# 1_power.net
KiCad netlist of a schematic drawn in Altium Designer
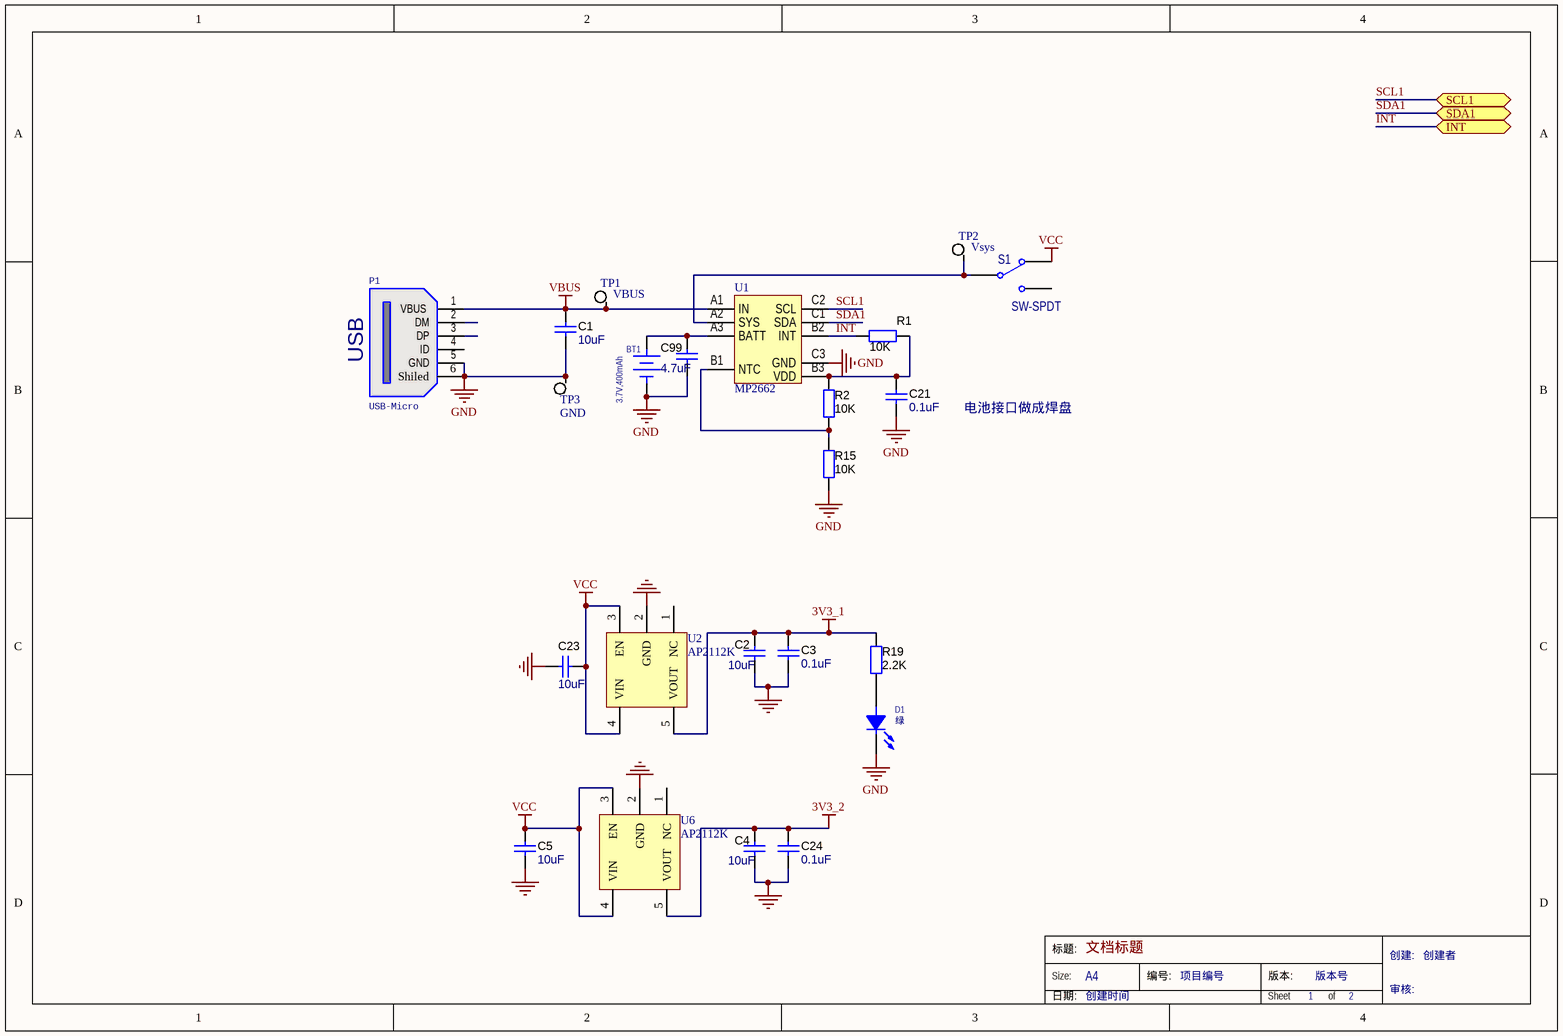
[diagram p0: 1.power.SchDoc]

(export (version "E")
  (design (tool "Eeschema 10.0.6"))
  (components
    (comp (ref "BT1")
      (value "3.7V,400mAh")
      (footprint "焊盘")
      (description "4.2V Li-lon")
      (fields (field (name "MANUFACTURER") "?"))
      (libsource (lib "03.常用器件") (part "Battery"))
    )
    (comp (ref "C1")
      (value "10uF")
      (footprint "0603")
      (description "CAP, CERM, 0.01uF, 100V, +/-5%, X7R, 0603")
      (fields (field (name "PARTNUMBER") "06031C103JAT2A") (field (name "MANUFACTURER") "AVX"))
      (libsource (lib "03.常用器件") (part "CAP1_npol"))
    )
    (comp (ref "C2")
      (value "10uF")
      (footprint "0603")
      (description "CAP, CERM, 0.01uF, 100V, +/-5%, X7R, 0603")
      (fields (field (name "PARTNUMBER") "06031C103JAT2A") (field (name "MANUFACTURER") "AVX"))
      (libsource (lib "03.常用器件") (part "CAP1_npol"))
    )
    (comp (ref "C3")
      (value "0.1uF")
      (footprint "0402")
      (description "CAP, CERM, 0.01uF, 100V, +/-5%, X7R, 0603")
      (fields (field (name "PARTNUMBER") "06031C103JAT2A") (field (name "MANUFACTURER") "AVX"))
      (libsource (lib "03.常用器件") (part "CAP1_npol"))
    )
    (comp (ref "C4")
      (value "10uF")
      (footprint "0603")
      (description "CAP, CERM, 0.01uF, 100V, +/-5%, X7R, 0603")
      (fields (field (name "PARTNUMBER") "06031C103JAT2A") (field (name "MANUFACTURER") "AVX"))
      (libsource (lib "03.常用器件") (part "CAP1_npol"))
    )
    (comp (ref "C5")
      (value "10uF")
      (footprint "0603")
      (description "CAP, CERM, 0.01uF, 100V, +/-5%, X7R, 0603")
      (fields (field (name "PARTNUMBER") "06031C103JAT2A") (field (name "MANUFACTURER") "AVX"))
      (libsource (lib "03.常用器件") (part "CAP1_npol"))
    )
    (comp (ref "C21")
      (value "0.1uF")
      (footprint "0603")
      (description "CAP, CERM, 0.01uF, 100V, +/-5%, X7R, 0603")
      (fields (field (name "PARTNUMBER") "06031C103JAT2A") (field (name "MANUFACTURER") "AVX"))
      (libsource (lib "03.常用器件") (part "CAP1_npol"))
    )
    (comp (ref "C23")
      (value "10uF")
      (footprint "0603")
      (description "CAP, CERM, 0.01uF, 100V, +/-5%, X7R, 0603")
      (fields (field (name "PARTNUMBER") "06031C103JAT2A") (field (name "MANUFACTURER") "AVX"))
      (libsource (lib "03.常用器件") (part "CAP1_npol"))
    )
    (comp (ref "C24")
      (value "0.1uF")
      (footprint "0402")
      (description "CAP, CERM, 0.01uF, 100V, +/-5%, X7R, 0603")
      (fields (field (name "PARTNUMBER") "06031C103JAT2A") (field (name "MANUFACTURER") "AVX"))
      (libsource (lib "03.常用器件") (part "CAP1_npol"))
    )
    (comp (ref "C99")
      (value "4.7uF")
      (footprint "0603")
      (description "CAP, CERM, 0.01uF, 100V, +/-5%, X7R, 0603")
      (fields (field (name "PARTNUMBER") "06031C103JAT2A") (field (name "MANUFACTURER") "AVX"))
      (libsource (lib "03.常用器件") (part "CAP1_npol"))
    )
    (comp (ref "D1")
      (value "绿")
      (footprint "0603LED")
      (fields (field (name "MANUFACTURER") "?"))
      (libsource (lib "03.常用器件") (part "LED1"))
    )
    (comp (ref "P1")
      (value "USB-Micro")
      (footprint "MICRO_USB2")
      (description "USB Connector")
      (libsource (lib "misc") (part "USB-Micro"))
    )
    (comp (ref "R1")
      (value "10K")
      (footprint "0402")
      (description "RES, 1.0k ohm, 5%, 0.1W, 0603")
      (fields
        (field (name "PARTNUMBER") "RC0603JR-071KL")
        (field (name "MANUFACTURER") "Yageo America")
        (field (name "PUBLISHER") "Texas Instruments")
      )
      (libsource (lib "") (part "RES1_1"))
    )
    (comp (ref "R2")
      (value "10K")
      (footprint "0402")
      (description "RES, 1.0k ohm, 5%, 0.1W, 0603")
      (fields
        (field (name "PARTNUMBER") "RC0603JR-071KL")
        (field (name "MANUFACTURER") "Yageo America")
        (field (name "PUBLISHER") "Texas Instruments")
      )
      (libsource (lib "03.常用器件") (part "RES1"))
    )
    (comp (ref "R15")
      (value "10K")
      (footprint "0402")
      (description "RES, 1.0k ohm, 5%, 0.1W, 0603")
      (fields
        (field (name "PARTNUMBER") "RC0603JR-071KL")
        (field (name "MANUFACTURER") "Yageo America")
        (field (name "PUBLISHER") "Texas Instruments")
      )
      (libsource (lib "03.常用器件") (part "RES1"))
    )
    (comp (ref "R19")
      (value "2.2K")
      (footprint "0402")
      (description "RES, 1.0k ohm, 5%, 0.1W, 0603")
      (fields
        (field (name "PARTNUMBER") "RC0603JR-071KL")
        (field (name "MANUFACTURER") "Yageo America")
        (field (name "PUBLISHER") "Texas Instruments")
      )
      (libsource (lib "03.常用器件") (part "RES1"))
    )
    (comp (ref "S1")
      (value "SW-SPDT")
      (footprint "SW2")
      (description "SPDT Subminiature Toggle Switch, Right Angle Mounting, Vertical Actuation")
      (fields (field (name "PUBLISHER") "Altium Limited"))
      (libsource (lib "Miscellaneous Devices") (part "SW-SPDT"))
    )
    (comp (ref "TP1")
      (value "VBUS")
      (footprint "测试点")
      (description "Test Point")
      (libsource (lib "my_Schlib") (part "TP"))
    )
    (comp (ref "TP2")
      (value "Vsys")
      (footprint "测试点")
      (description "Test Point")
      (libsource (lib "my_Schlib") (part "TP"))
    )
    (comp (ref "TP3")
      (value "GND")
      (footprint "测试点")
      (description "Test Point")
      (libsource (lib "my_Schlib") (part "TP"))
    )
    (comp (ref "U1") (value "MP2662") (footprint "WLCSP-9") (libsource (lib "Schlib1") (part "MP2662")))
    (comp (ref "U2") (value "AP2112K") (footprint "SOT89-5") (libsource (lib "Schlib1") (part "AP2112K")))
    (comp (ref "U6") (value "AP2112K") (footprint "SOT89-5") (libsource (lib "Schlib1") (part "AP2112K")))
  )
  (nets
    (net (code "1") (name "/INT") (class "Default")
      (node (ref "R1") (pin "1") (pinfunction "1_1") (pintype "passive"))
      (node (ref "U1") (pin "B2") (pinfunction "INT_B2") (pintype "passive"))
    )
    (net (code "2") (name "/SCL1") (class "Default")
      (node (ref "U1") (pin "C2") (pinfunction "SCL_C2") (pintype "passive"))
    )
    (net (code "3") (name "/SDA1") (class "Default")
      (node (ref "U1") (pin "C1") (pinfunction "SDA_C1") (pintype "passive"))
    )
    (net (code "4") (name "3V3_1") (class "Default")
      (node (ref "C2") (pin "1") (pinfunction "1_1") (pintype "passive"))
      (node (ref "C3") (pin "2") (pinfunction "2_2") (pintype "passive"))
      (node (ref "R19") (pin "1") (pinfunction "1_1") (pintype "passive"))
      (node (ref "U2") (pin "5") (pinfunction "VOUT_5") (pintype "passive"))
    )
    (net (code "5") (name "3V3_2") (class "Default")
      (node (ref "C24") (pin "2") (pinfunction "2_2") (pintype "passive"))
      (node (ref "C4") (pin "1") (pinfunction "1_1") (pintype "passive"))
      (node (ref "U6") (pin "5") (pinfunction "VOUT_5") (pintype "passive"))
    )
    (net (code "6") (name "GND") (class "Default")
      (node (ref "BT1") (pin "2") (pinfunction "-_2") (pintype "passive"))
      (node (ref "C1") (pin "2") (pinfunction "2_2") (pintype "passive"))
      (node (ref "C2") (pin "2") (pinfunction "2_2") (pintype "passive"))
      (node (ref "C21") (pin "2") (pinfunction "2_2") (pintype "passive"))
      (node (ref "C23") (pin "2") (pinfunction "2_2") (pintype "passive"))
      (node (ref "C24") (pin "1") (pinfunction "1_1") (pintype "passive"))
      (node (ref "C3") (pin "1") (pinfunction "1_1") (pintype "passive"))
      (node (ref "C4") (pin "2") (pinfunction "2_2") (pintype "passive"))
      (node (ref "C5") (pin "2") (pinfunction "2_2") (pintype "passive"))
      (node (ref "C99") (pin "2") (pinfunction "2_2") (pintype "passive"))
      (node (ref "D1") (pin "C") (pinfunction "CATHODE_C") (pintype "passive"))
      (node (ref "P1") (pin "5") (pinfunction "GND_5") (pintype "passive"))
      (node (ref "P1") (pin "6") (pinfunction "Shiled_6") (pintype "passive"))
      (node (ref "R15") (pin "2") (pinfunction "2_2") (pintype "passive"))
      (node (ref "TP3") (pin "1") (pinfunction "1_1") (pintype "passive"))
      (node (ref "U1") (pin "C3") (pinfunction "GND_C3") (pintype "passive"))
      (node (ref "U2") (pin "2") (pinfunction "GND_2") (pintype "passive"))
      (node (ref "U6") (pin "2") (pinfunction "GND_2") (pintype "passive"))
    )
    (net (code "7") (name "Net-(BT1-+)") (class "Default")
      (node (ref "BT1") (pin "1") (pinfunction "+_1") (pintype "passive"))
      (node (ref "C99") (pin "1") (pinfunction "1_1") (pintype "passive"))
      (node (ref "U1") (pin "A3") (pinfunction "BATT_A3") (pintype "passive"))
    )
    (net (code "8") (name "Net-(D1-ANODE)") (class "Default")
      (node (ref "D1") (pin "A") (pinfunction "ANODE_A") (pintype "passive"))
      (node (ref "R19") (pin "2") (pinfunction "2_2") (pintype "passive"))
    )
    (net (code "9") (name "Net-(U1-NTC)") (class "Default")
      (node (ref "R15") (pin "1") (pinfunction "1_1") (pintype "passive"))
      (node (ref "R2") (pin "2") (pinfunction "2_2") (pintype "passive"))
      (node (ref "U1") (pin "B1") (pinfunction "NTC_B1") (pintype "power_in"))
    )
    (net (code "10") (name "Net-(U1-SYS)") (class "Default")
      (node (ref "S1") (pin "2") (pinfunction "2_2") (pintype "passive"))
      (node (ref "TP2") (pin "1") (pinfunction "1_1") (pintype "passive"))
      (node (ref "U1") (pin "A2") (pinfunction "SYS_A2") (pintype "passive"))
    )
    (net (code "11") (name "Net-(U1-VDD)") (class "Default")
      (node (ref "C21") (pin "1") (pinfunction "1_1") (pintype "passive"))
      (node (ref "R1") (pin "2") (pinfunction "2_2") (pintype "passive"))
      (node (ref "R2") (pin "1") (pinfunction "1_1") (pintype "passive"))
      (node (ref "U1") (pin "B3") (pinfunction "VDD_B3") (pintype "passive"))
    )
    (net (code "12") (name "VBUS") (class "Default")
      (node (ref "C1") (pin "1") (pinfunction "1_1") (pintype "passive"))
      (node (ref "P1") (pin "1") (pinfunction "VBUS_1") (pintype "passive"))
      (node (ref "TP1") (pin "1") (pinfunction "1_1") (pintype "passive"))
      (node (ref "U1") (pin "A1") (pinfunction "IN_A1") (pintype "passive"))
    )
    (net (code "13") (name "VCC") (class "Default")
      (node (ref "C23") (pin "1") (pinfunction "1_1") (pintype "passive"))
      (node (ref "C5") (pin "1") (pinfunction "1_1") (pintype "passive"))
      (node (ref "S1") (pin "3") (pinfunction "3_3") (pintype "passive"))
      (node (ref "U2") (pin "3") (pinfunction "EN_3") (pintype "passive"))
      (node (ref "U2") (pin "4") (pinfunction "VIN_4") (pintype "passive"))
      (node (ref "U6") (pin "3") (pinfunction "EN_3") (pintype "passive"))
      (node (ref "U6") (pin "4") (pinfunction "VIN_4") (pintype "passive"))
    )
    (net (code "14") (name "unconnected-(P1-DM-Pad2)") (class "Default")
      (node (ref "P1") (pin "2") (pinfunction "DM_2") (pintype "passive"))
    )
    (net (code "15") (name "unconnected-(P1-DP-Pad3)") (class "Default")
      (node (ref "P1") (pin "3") (pinfunction "DP_3") (pintype "passive"))
    )
    (net (code "16") (name "unconnected-(P1-ID-Pad4)") (class "Default")
      (node (ref "P1") (pin "4") (pinfunction "ID_4") (pintype "passive"))
    )
    (net (code "17") (name "unconnected-(S1-Pad1)") (class "Default")
      (node (ref "S1") (pin "1") (pinfunction "1_1") (pintype "passive"))
    )
    (net (code "18") (name "unconnected-(U2-NC-Pad1)") (class "Default")
      (node (ref "U2") (pin "1") (pinfunction "NC_1") (pintype "passive"))
    )
    (net (code "19") (name "unconnected-(U6-NC-Pad1)") (class "Default")
      (node (ref "U6") (pin "1") (pinfunction "NC_1") (pintype "passive"))
    )
  )
)
